# nails_schematic_v2.net
KiCad netlist of a schematic drawn in Altium Designer
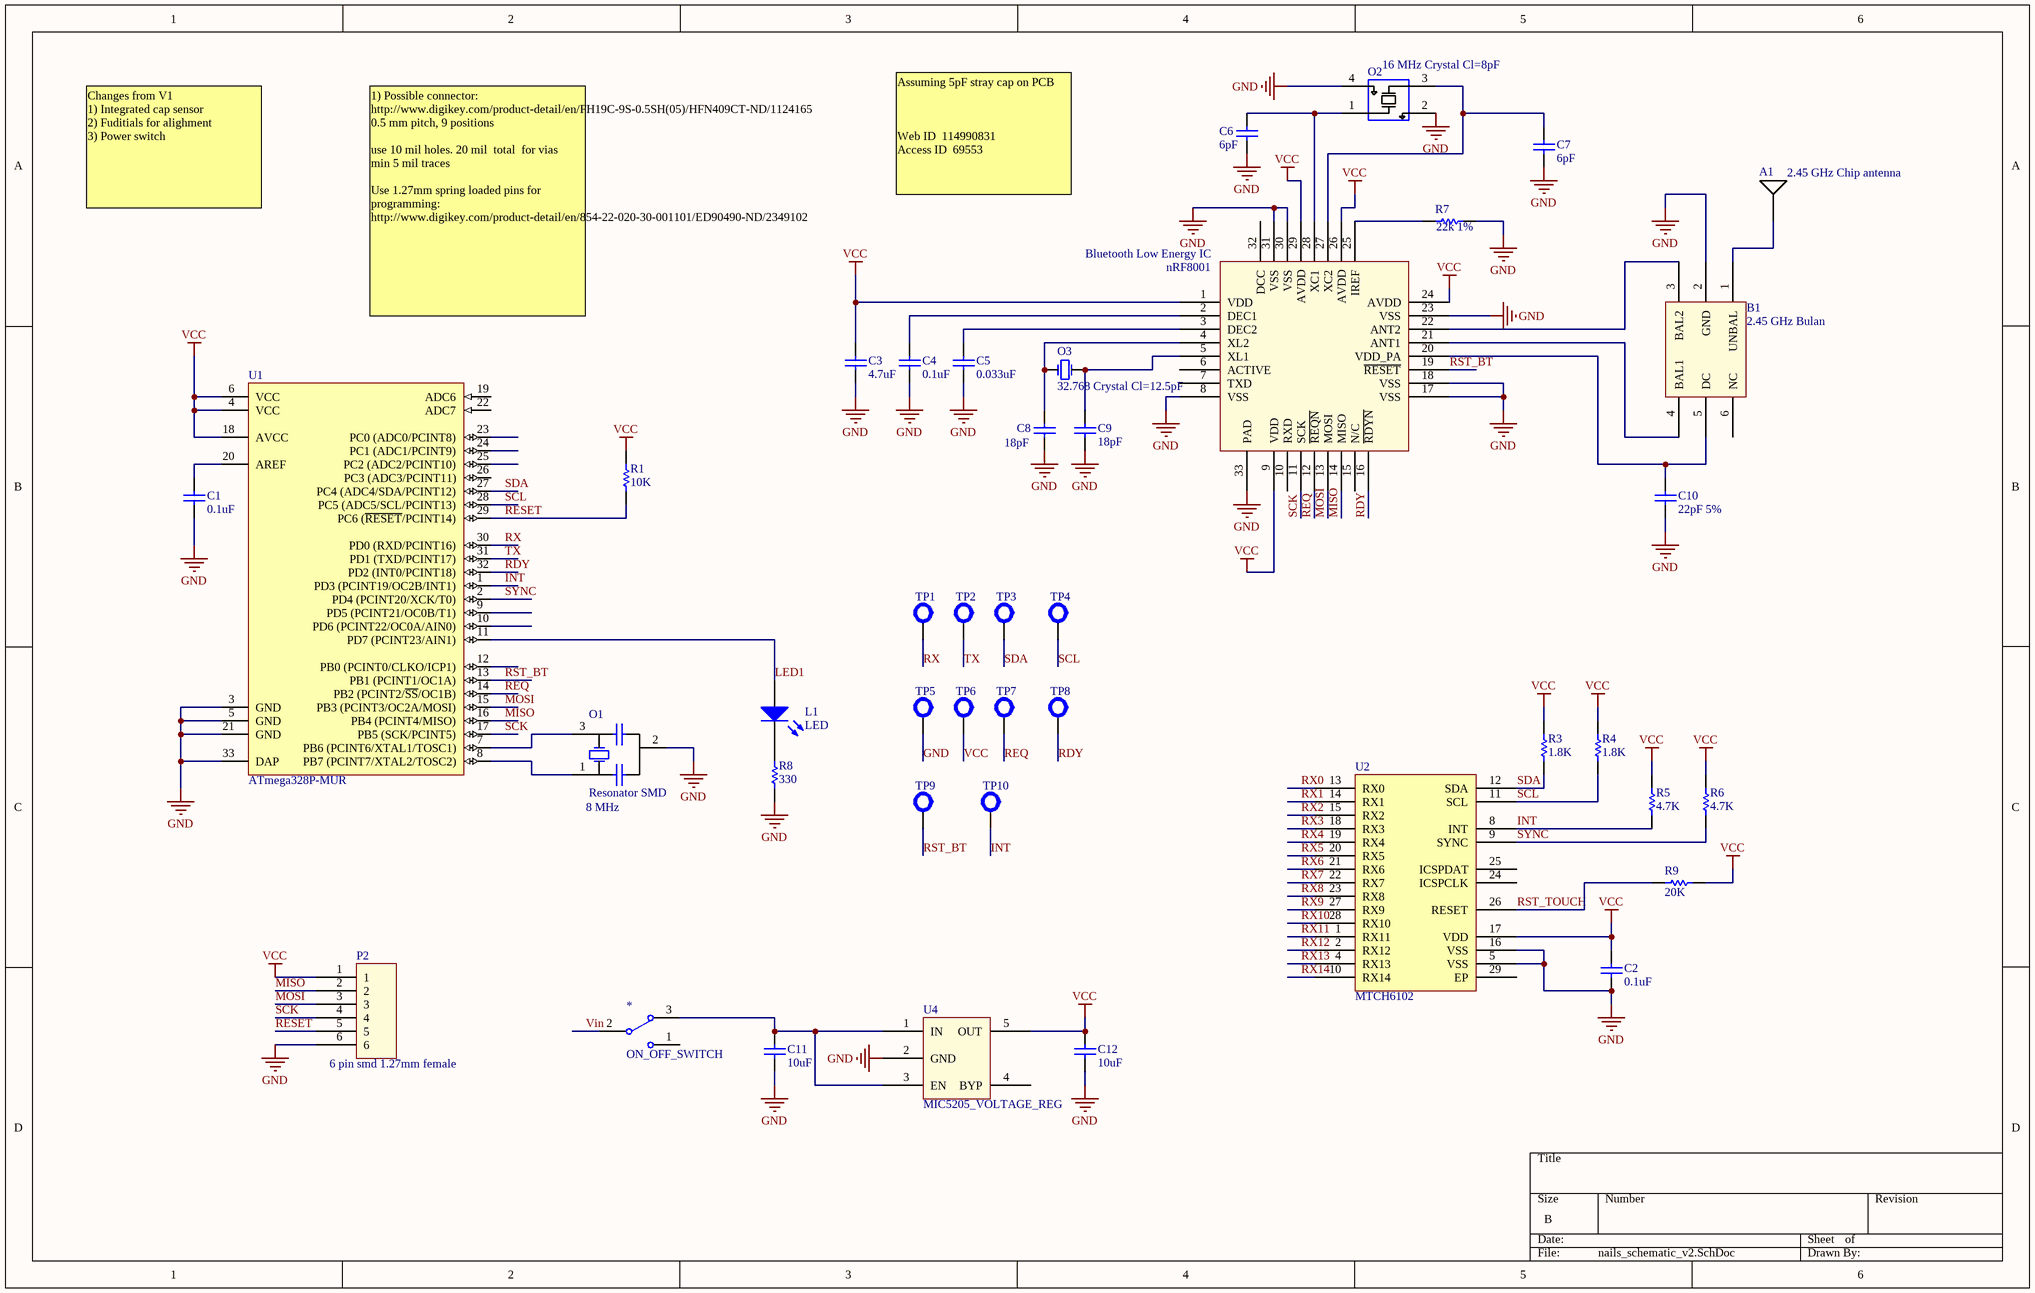
[diagram p0: nails_schematic_v2.SchDoc]

(export (version "E")
  (design (tool "Eeschema 10.0.6"))
  (components
    (comp (ref "*")
      (value "ON_OFF_SWITCH")
      (footprint "SWTICH_SMD_SIDE")
      (description "DPDT SMD Side Switch 240 mA at 5V")
      (libsource (lib "Artem_Library") (part "ON_OFF_SWITCH"))
    )
    (comp (ref "A1")
      (value "2.45 GHz Chip antenna")
      (footprint "2450AT18A100E")
      (description "for Bluetooth")
      (libsource (lib "Artem_Library") (part "2.45 GHz Chip antenna"))
    )
    (comp (ref "B1")
      (value "2.45 GHz Bulan")
      (footprint "2450BM14A0002")
      (description "for nRF8001 chip")
      (libsource (lib "Artem_Library") (part "2.45 GHz Bulan"))
    )
    (comp (ref "Bluetooth Low Energy IC")
      (value "nRF8001")
      (footprint "QFN32_W_GND")
      (libsource (lib "Artem_Library") (part "nRF8001"))
    )
    (comp (ref "C1")
      (value "0.1uF")
      (footprint "0402W")
      (description "SMD Cap 1206")
      (libsource (lib "Artem_Library") (part "Capacitor"))
    )
    (comp (ref "C2")
      (value "0.1uF")
      (footprint "0402W")
      (description "SMD Cap 1206")
      (libsource (lib "Artem_Library") (part "Capacitor"))
    )
    (comp (ref "C3")
      (value "4.7uF")
      (footprint "0402W")
      (description "SMD Cap 1206")
      (libsource (lib "Artem_Library") (part "Capacitor"))
    )
    (comp (ref "C4")
      (value "0.1uF")
      (footprint "0402W")
      (description "SMD Cap 1206")
      (libsource (lib "Artem_Library") (part "Capacitor"))
    )
    (comp (ref "C5")
      (value "0.033uF")
      (footprint "0402W")
      (description "SMD Cap 1206")
      (libsource (lib "Artem_Library") (part "Capacitor"))
    )
    (comp (ref "C6")
      (value "6pF")
      (footprint "0402W")
      (description "SMD Cap 1206")
      (libsource (lib "Artem_Library") (part "Capacitor"))
    )
    (comp (ref "C7")
      (value "6pF")
      (footprint "0402W")
      (description "SMD Cap 1206")
      (libsource (lib "Artem_Library") (part "Capacitor"))
    )
    (comp (ref "C8")
      (value "18pF")
      (footprint "0402W")
      (description "SMD Cap 1206")
      (libsource (lib "Artem_Library") (part "Capacitor"))
    )
    (comp (ref "C9")
      (value "18pF")
      (footprint "0402W")
      (description "SMD Cap 1206")
      (libsource (lib "Artem_Library") (part "Capacitor"))
    )
    (comp (ref "C10")
      (value "22pF 5%")
      (footprint "0402W")
      (description "SMD Cap 1206")
      (libsource (lib "Artem_Library") (part "Capacitor"))
    )
    (comp (ref "C11")
      (value "10uF")
      (footprint "0402W")
      (description "SMD Cap 1206")
      (libsource (lib "Artem_Library") (part "Capacitor"))
    )
    (comp (ref "C12")
      (value "10uF")
      (footprint "0402W")
      (description "SMD Cap 1206")
      (libsource (lib "Artem_Library") (part "Capacitor"))
    )
    (comp (ref "L1")
      (value "LED")
      (footprint "0402W")
      (description "LED SMD 1206/0603")
      (libsource (lib "Artem_Library") (part "LED"))
    )
    (comp (ref "O1")
      (value "Resonator SMD")
      (footprint "Resonator SMD")
      (description "Build in caps")
      (libsource (lib "Artem_Library") (part "Resonator SMD"))
    )
    (comp (ref "O2")
      (value "16 MHz Crystal Cl=8pF")
      (footprint "2.5 x 2.0 crystal")
      (description "For BLE use")
      (libsource (lib "Artem_Library") (part "16 MHz Crystal Wireless"))
    )
    (comp (ref "O3")
      (value "32.768 Crystal Cl=12.5pF")
      (footprint "32.768 Crystal")
      (libsource (lib "Artem_Library") (part "32.768 Crystal"))
    )
    (comp (ref "P2")
      (value "6 pin smd 1.27mm female")
      (footprint "6pos 1.27mm")
      (libsource (lib "Artem_Library") (part "6 pin smd 1.27mm female"))
    )
    (comp (ref "R1") (value "10K") (footprint "0402W") (libsource (lib "Artem_Library") (part "Resistor")))
    (comp (ref "R3") (value "1.8K") (footprint "0402W") (libsource (lib "Artem_Library") (part "Resistor")))
    (comp (ref "R4") (value "1.8K") (footprint "0402W") (libsource (lib "Artem_Library") (part "Resistor")))
    (comp (ref "R5") (value "4.7K") (footprint "0402W") (libsource (lib "Artem_Library") (part "Resistor")))
    (comp (ref "R6") (value "4.7K") (footprint "0402W") (libsource (lib "Artem_Library") (part "Resistor")))
    (comp (ref "R7") (value "22k 1%") (footprint "0402W") (libsource (lib "Artem_Library") (part "Resistor")))
    (comp (ref "R8") (value "330") (footprint "0402W") (libsource (lib "Artem_Library") (part "Resistor")))
    (comp (ref "R9") (value "20K") (footprint "0402W") (libsource (lib "Artem_Library") (part "Resistor")))
    (comp (ref "TP1")
      (value "Test point small")
      (footprint "TEST POINT SMD SUPER SMALL")
      (libsource (lib "Artem_Library") (part "Test point small"))
    )
    (comp (ref "TP2")
      (value "Test point small")
      (footprint "TEST POINT SMD SUPER SMALL")
      (libsource (lib "Artem_Library") (part "Test point small"))
    )
    (comp (ref "TP3")
      (value "Test point small")
      (footprint "TEST POINT SMD SUPER SMALL")
      (libsource (lib "Artem_Library") (part "Test point small"))
    )
    (comp (ref "TP4")
      (value "Test point small")
      (footprint "TEST POINT SMD SUPER SMALL")
      (libsource (lib "Artem_Library") (part "Test point small"))
    )
    (comp (ref "TP5")
      (value "Test point small")
      (footprint "TEST POINT SMD SUPER SMALL")
      (libsource (lib "Artem_Library") (part "Test point small"))
    )
    (comp (ref "TP6")
      (value "Test point small")
      (footprint "TEST POINT SMD SUPER SMALL")
      (libsource (lib "Artem_Library") (part "Test point small"))
    )
    (comp (ref "TP7")
      (value "Test point small")
      (footprint "TEST POINT SMD SUPER SMALL")
      (libsource (lib "Artem_Library") (part "Test point small"))
    )
    (comp (ref "TP8")
      (value "Test point small")
      (footprint "TEST POINT SMD SUPER SMALL")
      (libsource (lib "Artem_Library") (part "Test point small"))
    )
    (comp (ref "TP9")
      (value "Test point small")
      (footprint "TEST POINT SMD SUPER SMALL")
      (libsource (lib "Artem_Library") (part "Test point small"))
    )
    (comp (ref "TP10")
      (value "Test point small")
      (footprint "TEST POINT SMD SUPER SMALL")
      (libsource (lib "Artem_Library") (part "Test point small"))
    )
    (comp (ref "U1")
      (value "ATmega328P-MUR")
      (footprint "32M1-A_M")
      (libsource (lib "Atmel Microcontroller 8-Bit megaAVR") (part "ATmega328P-MUR"))
    )
    (comp (ref "U2")
      (value "MTCH6102")
      (footprint "QFN28_no_gnd_conn")
      (libsource (lib "Artem_Library") (part "MTCH6102"))
    )
    (comp (ref "U4")
      (value "MIC5205_VOLTAGE_REG")
      (footprint "SOT-23-5")
      (description "5V LDO SMD")
      (libsource (lib "Artem_Library") (part "MIC5205_VOLTAGE_REG"))
    )
  )
  (nets
    (net (code "1") (name "/INT") (class "Default")
      (node (ref "R5") (pin "1") (pinfunction "1_1") (pintype "passive"))
      (node (ref "TP10") (pin "0") (pinfunction "0_0") (pintype "passive"))
      (node (ref "U1") (pin "1") (pinfunction "PD3_(PCINT19/OC2B/INT1)_1") (pintype "bidirectional"))
      (node (ref "U2") (pin "8") (pinfunction "INT_8") (pintype "passive"))
    )
    (net (code "2") (name "/LED1") (class "Default")
      (node (ref "L1") (pin "1") (pinfunction "A_1") (pintype "passive"))
      (node (ref "U1") (pin "11") (pinfunction "PD7_(PCINT23/AIN1)_11") (pintype "bidirectional"))
    )
    (net (code "3") (name "/MISO") (class "Default")
      (node (ref "Bluetooth Low Energy IC") (pin "14") (pinfunction "MISO_14") (pintype "passive"))
      (node (ref "P2") (pin "2") (pinfunction "2_2") (pintype "passive"))
      (node (ref "U1") (pin "16") (pinfunction "PB4_(PCINT4/MISO)_16") (pintype "bidirectional"))
    )
    (net (code "4") (name "/MOSI") (class "Default")
      (node (ref "Bluetooth Low Energy IC") (pin "13") (pinfunction "MOSI_13") (pintype "passive"))
      (node (ref "P2") (pin "3") (pinfunction "3_3") (pintype "passive"))
      (node (ref "U1") (pin "15") (pinfunction "PB3_(PCINT3/OC2A/MOSI)_15") (pintype "bidirectional"))
    )
    (net (code "5") (name "/RDY") (class "Default")
      (node (ref "Bluetooth Low Energy IC") (pin "16") (pinfunction "~{RDYN}_16") (pintype "passive"))
      (node (ref "TP8") (pin "0") (pinfunction "0_0") (pintype "passive"))
      (node (ref "U1") (pin "32") (pinfunction "PD2_(INT0/PCINT18)_32") (pintype "bidirectional"))
    )
    (net (code "6") (name "/REQ") (class "Default")
      (node (ref "Bluetooth Low Energy IC") (pin "12") (pinfunction "~{REQN}_12") (pintype "passive"))
      (node (ref "TP7") (pin "0") (pinfunction "0_0") (pintype "passive"))
      (node (ref "U1") (pin "14") (pinfunction "PB2_(PCINT2/~{SS}/OC1B)_14") (pintype "bidirectional"))
    )
    (net (code "7") (name "/RESET") (class "Default")
      (node (ref "P2") (pin "5") (pinfunction "5_5") (pintype "passive"))
      (node (ref "R1") (pin "1") (pinfunction "1_1") (pintype "passive"))
      (node (ref "U1") (pin "29") (pinfunction "PC6_(~{RESET}/PCINT14)_29") (pintype "bidirectional"))
    )
    (net (code "8") (name "/RST_BT") (class "Default")
      (node (ref "Bluetooth Low Energy IC") (pin "19") (pinfunction "~{RESET}_19") (pintype "passive"))
      (node (ref "TP9") (pin "0") (pinfunction "0_0") (pintype "passive"))
      (node (ref "U1") (pin "13") (pinfunction "PB1_(PCINT1/OC1A)_13") (pintype "bidirectional"))
    )
    (net (code "9") (name "/RST_TOUCH") (class "Default")
      (node (ref "R9") (pin "2") (pinfunction "2_2") (pintype "passive"))
      (node (ref "U2") (pin "26") (pinfunction "RESET_26") (pintype "passive"))
    )
    (net (code "10") (name "/RX") (class "Default")
      (node (ref "TP1") (pin "0") (pinfunction "0_0") (pintype "passive"))
      (node (ref "U1") (pin "30") (pinfunction "PD0_(RXD/PCINT16)_30") (pintype "bidirectional"))
    )
    (net (code "11") (name "/RX0") (class "Default")
      (node (ref "U2") (pin "13") (pinfunction "RX0_13") (pintype "passive"))
    )
    (net (code "12") (name "/RX1") (class "Default")
      (node (ref "U2") (pin "14") (pinfunction "RX1_14") (pintype "passive"))
    )
    (net (code "13") (name "/RX2") (class "Default")
      (node (ref "U2") (pin "15") (pinfunction "RX2_15") (pintype "passive"))
    )
    (net (code "14") (name "/RX3") (class "Default")
      (node (ref "U2") (pin "18") (pinfunction "RX3_18") (pintype "passive"))
    )
    (net (code "15") (name "/RX4") (class "Default")
      (node (ref "U2") (pin "19") (pinfunction "RX4_19") (pintype "passive"))
    )
    (net (code "16") (name "/RX5") (class "Default")
      (node (ref "U2") (pin "20") (pinfunction "RX5_20") (pintype "passive"))
    )
    (net (code "17") (name "/RX6") (class "Default")
      (node (ref "U2") (pin "21") (pinfunction "RX6_21") (pintype "passive"))
    )
    (net (code "18") (name "/RX7") (class "Default")
      (node (ref "U2") (pin "22") (pinfunction "RX7_22") (pintype "passive"))
    )
    (net (code "19") (name "/RX8") (class "Default")
      (node (ref "U2") (pin "23") (pinfunction "RX8_23") (pintype "passive"))
    )
    (net (code "20") (name "/RX9") (class "Default")
      (node (ref "U2") (pin "27") (pinfunction "RX9_27") (pintype "passive"))
    )
    (net (code "21") (name "/RX10") (class "Default")
      (node (ref "U2") (pin "28") (pinfunction "RX10_28") (pintype "passive"))
    )
    (net (code "22") (name "/RX11") (class "Default")
      (node (ref "U2") (pin "1") (pinfunction "RX11_1") (pintype "passive"))
    )
    (net (code "23") (name "/RX12") (class "Default")
      (node (ref "U2") (pin "2") (pinfunction "RX12_2") (pintype "passive"))
    )
    (net (code "24") (name "/RX13") (class "Default")
      (node (ref "U2") (pin "4") (pinfunction "RX13_4") (pintype "passive"))
    )
    (net (code "25") (name "/RX14") (class "Default")
      (node (ref "U2") (pin "10") (pinfunction "RX14_10") (pintype "passive"))
    )
    (net (code "26") (name "/SCK") (class "Default")
      (node (ref "Bluetooth Low Energy IC") (pin "11") (pinfunction "SCK_11") (pintype "passive"))
      (node (ref "P2") (pin "4") (pinfunction "4_4") (pintype "passive"))
      (node (ref "U1") (pin "17") (pinfunction "PB5_(SCK/PCINT5)_17") (pintype "bidirectional"))
    )
    (net (code "27") (name "/SCL") (class "Default")
      (node (ref "R4") (pin "1") (pinfunction "1_1") (pintype "passive"))
      (node (ref "TP4") (pin "0") (pinfunction "0_0") (pintype "passive"))
      (node (ref "U1") (pin "28") (pinfunction "PC5_(ADC5/SCL/PCINT13)_28") (pintype "bidirectional"))
      (node (ref "U2") (pin "11") (pinfunction "SCL_11") (pintype "passive"))
    )
    (net (code "28") (name "/SDA") (class "Default")
      (node (ref "R3") (pin "1") (pinfunction "1_1") (pintype "passive"))
      (node (ref "TP3") (pin "0") (pinfunction "0_0") (pintype "passive"))
      (node (ref "U1") (pin "27") (pinfunction "PC4_(ADC4/SDA/PCINT12)_27") (pintype "bidirectional"))
      (node (ref "U2") (pin "12") (pinfunction "SDA_12") (pintype "passive"))
    )
    (net (code "29") (name "/SYNC") (class "Default")
      (node (ref "R6") (pin "1") (pinfunction "1_1") (pintype "passive"))
      (node (ref "U1") (pin "2") (pinfunction "PD4_(PCINT20/XCK/T0)_2") (pintype "bidirectional"))
      (node (ref "U2") (pin "9") (pinfunction "SYNC_9") (pintype "passive"))
    )
    (net (code "30") (name "/TX") (class "Default")
      (node (ref "TP2") (pin "0") (pinfunction "0_0") (pintype "passive"))
      (node (ref "U1") (pin "31") (pinfunction "PD1_(TXD/PCINT17)_31") (pintype "bidirectional"))
    )
    (net (code "31") (name "/Vin") (class "Default")
      (node (ref "*") (pin "2") (pinfunction "2_2") (pintype "passive"))
    )
    (net (code "32") (name "GND") (class "Default")
      (node (ref "B1") (pin "2") (pinfunction "GND_2") (pintype "passive"))
      (node (ref "Bluetooth Low Energy IC") (pin "17") (pinfunction "VSS_17") (pintype "passive"))
      (node (ref "Bluetooth Low Energy IC") (pin "18") (pinfunction "VSS_18") (pintype "passive"))
      (node (ref "Bluetooth Low Energy IC") (pin "23") (pinfunction "VSS_23") (pintype "passive"))
      (node (ref "Bluetooth Low Energy IC") (pin "30") (pinfunction "VSS_30") (pintype "passive"))
      (node (ref "Bluetooth Low Energy IC") (pin "31") (pinfunction "VSS_31") (pintype "passive"))
      (node (ref "Bluetooth Low Energy IC") (pin "33") (pinfunction "PAD_33") (pintype "passive"))
      (node (ref "Bluetooth Low Energy IC") (pin "8") (pinfunction "VSS_8") (pintype "passive"))
      (node (ref "C1") (pin "1") (pinfunction "1_1") (pintype "passive"))
      (node (ref "C10") (pin "1") (pinfunction "1_1") (pintype "passive"))
      (node (ref "C11") (pin "1") (pinfunction "1_1") (pintype "passive"))
      (node (ref "C12") (pin "1") (pinfunction "1_1") (pintype "passive"))
      (node (ref "C2") (pin "1") (pinfunction "1_1") (pintype "passive"))
      (node (ref "C3") (pin "1") (pinfunction "1_1") (pintype "passive"))
      (node (ref "C4") (pin "1") (pinfunction "1_1") (pintype "passive"))
      (node (ref "C5") (pin "1") (pinfunction "1_1") (pintype "passive"))
      (node (ref "C6") (pin "1") (pinfunction "1_1") (pintype "passive"))
      (node (ref "C7") (pin "1") (pinfunction "1_1") (pintype "passive"))
      (node (ref "C8") (pin "1") (pinfunction "1_1") (pintype "passive"))
      (node (ref "C9") (pin "1") (pinfunction "1_1") (pintype "passive"))
      (node (ref "O1") (pin "2") (pinfunction "2_2") (pintype "passive"))
      (node (ref "O2") (pin "2") (pinfunction "Gnd_2") (pintype "passive"))
      (node (ref "O2") (pin "4") (pinfunction "Gnd_4") (pintype "passive"))
      (node (ref "P2") (pin "6") (pinfunction "6_6") (pintype "passive"))
      (node (ref "R7") (pin "1") (pinfunction "1_1") (pintype "passive"))
      (node (ref "R8") (pin "1") (pinfunction "1_1") (pintype "passive"))
      (node (ref "TP5") (pin "0") (pinfunction "0_0") (pintype "passive"))
      (node (ref "U1") (pin "21") (pinfunction "GND_21") (pintype "power_in"))
      (node (ref "U1") (pin "3") (pinfunction "GND_3") (pintype "power_in"))
      (node (ref "U1") (pin "33") (pinfunction "DAP_33") (pintype "power_in"))
      (node (ref "U1") (pin "5") (pinfunction "GND_5") (pintype "power_in"))
      (node (ref "U2") (pin "16") (pinfunction "VSS_16") (pintype "passive"))
      (node (ref "U2") (pin "5") (pinfunction "VSS_5") (pintype "passive"))
      (node (ref "U4") (pin "2") (pinfunction "GND_2") (pintype "passive"))
    )
    (net (code "33") (name "Net-(B1-BAL1)") (class "Default")
      (node (ref "B1") (pin "4") (pinfunction "BAL1_4") (pintype "passive"))
      (node (ref "Bluetooth Low Energy IC") (pin "21") (pinfunction "ANT1_21") (pintype "passive"))
    )
    (net (code "34") (name "Net-(B1-BAL2)") (class "Default")
      (node (ref "B1") (pin "3") (pinfunction "BAL2_3") (pintype "passive"))
      (node (ref "Bluetooth Low Energy IC") (pin "22") (pinfunction "ANT2_22") (pintype "passive"))
    )
    (net (code "35") (name "Net-(B1-DC)") (class "Default")
      (node (ref "B1") (pin "5") (pinfunction "DC_5") (pintype "passive"))
      (node (ref "Bluetooth Low Energy IC") (pin "20") (pinfunction "VDD_PA_20") (pintype "passive"))
      (node (ref "C10") (pin "2") (pinfunction "2_2") (pintype "passive"))
    )
    (net (code "36") (name "Net-(B1-UNBAL)") (class "Default")
      (node (ref "A1") (pin "1") (pinfunction "1_1") (pintype "passive"))
      (node (ref "B1") (pin "1") (pinfunction "UNBAL_1") (pintype "passive"))
    )
    (net (code "37") (name "Net-(Bluetooth Low Energy IC-DEC1)") (class "Default")
      (node (ref "Bluetooth Low Energy IC") (pin "2") (pinfunction "DEC1_2") (pintype "passive"))
      (node (ref "C4") (pin "2") (pinfunction "2_2") (pintype "passive"))
    )
    (net (code "38") (name "Net-(Bluetooth Low Energy IC-DEC2)") (class "Default")
      (node (ref "Bluetooth Low Energy IC") (pin "3") (pinfunction "DEC2_3") (pintype "passive"))
      (node (ref "C5") (pin "2") (pinfunction "2_2") (pintype "passive"))
    )
    (net (code "39") (name "Net-(Bluetooth Low Energy IC-IREF)") (class "Default")
      (node (ref "Bluetooth Low Energy IC") (pin "25") (pinfunction "IREF_25") (pintype "passive"))
      (node (ref "R7") (pin "2") (pinfunction "2_2") (pintype "passive"))
    )
    (net (code "40") (name "Net-(Bluetooth Low Energy IC-XC1)") (class "Default")
      (node (ref "Bluetooth Low Energy IC") (pin "28") (pinfunction "XC1_28") (pintype "passive"))
      (node (ref "C6") (pin "2") (pinfunction "2_2") (pintype "passive"))
      (node (ref "O2") (pin "1") (pinfunction "XIN_1") (pintype "passive"))
    )
    (net (code "41") (name "Net-(Bluetooth Low Energy IC-XC2)") (class "Default")
      (node (ref "Bluetooth Low Energy IC") (pin "27") (pinfunction "XC2_27") (pintype "passive"))
      (node (ref "C7") (pin "2") (pinfunction "2_2") (pintype "passive"))
      (node (ref "O2") (pin "3") (pinfunction "XOUT_3") (pintype "passive"))
    )
    (net (code "42") (name "Net-(Bluetooth Low Energy IC-XL1)") (class "Default")
      (node (ref "Bluetooth Low Energy IC") (pin "5") (pinfunction "XL1_5") (pintype "passive"))
      (node (ref "C9") (pin "2") (pinfunction "2_2") (pintype "passive"))
      (node (ref "O3") (pin "2") (pinfunction "2_2") (pintype "passive"))
    )
    (net (code "43") (name "Net-(Bluetooth Low Energy IC-XL2)") (class "Default")
      (node (ref "Bluetooth Low Energy IC") (pin "4") (pinfunction "XL2_4") (pintype "passive"))
      (node (ref "C8") (pin "2") (pinfunction "2_2") (pintype "passive"))
      (node (ref "O3") (pin "1") (pinfunction "1_1") (pintype "passive"))
    )
    (net (code "44") (name "Net-(L1-K)") (class "Default")
      (node (ref "L1") (pin "2") (pinfunction "K_2") (pintype "passive"))
      (node (ref "R8") (pin "2") (pinfunction "2_2") (pintype "passive"))
    )
    (net (code "45") (name "Net-(U1-AREF)") (class "Default")
      (node (ref "C1") (pin "2") (pinfunction "2_2") (pintype "passive"))
      (node (ref "U1") (pin "20") (pinfunction "AREF_20") (pintype "passive"))
    )
    (net (code "46") (name "Net-(U1-PB6_(PCINT6{slash}XTAL1{slash}TOSC1))") (class "Default")
      (node (ref "O1") (pin "3") (pinfunction "3_3") (pintype "passive"))
      (node (ref "U1") (pin "7") (pinfunction "PB6_(PCINT6/XTAL1/TOSC1)_7") (pintype "bidirectional"))
    )
    (net (code "47") (name "Net-(U1-PB7_(PCINT7{slash}XTAL2{slash}TOSC2))") (class "Default")
      (node (ref "O1") (pin "1") (pinfunction "1_1") (pintype "passive"))
      (node (ref "U1") (pin "8") (pinfunction "PB7_(PCINT7/XTAL2/TOSC2)_8") (pintype "bidirectional"))
    )
    (net (code "48") (name "Net-(U4-EN)") (class "Default")
      (node (ref "*") (pin "3") (pinfunction "3_3") (pintype "passive"))
      (node (ref "C11") (pin "2") (pinfunction "2_2") (pintype "passive"))
      (node (ref "U4") (pin "1") (pinfunction "IN_1") (pintype "passive"))
      (node (ref "U4") (pin "3") (pinfunction "EN_3") (pintype "passive"))
    )
    (net (code "49") (name "VCC") (class "Default")
      (node (ref "Bluetooth Low Energy IC") (pin "1") (pinfunction "VDD_1") (pintype "passive"))
      (node (ref "Bluetooth Low Energy IC") (pin "24") (pinfunction "AVDD_24") (pintype "passive"))
      (node (ref "Bluetooth Low Energy IC") (pin "26") (pinfunction "AVDD_26") (pintype "passive"))
      (node (ref "Bluetooth Low Energy IC") (pin "29") (pinfunction "AVDD_29") (pintype "passive"))
      (node (ref "Bluetooth Low Energy IC") (pin "9") (pinfunction "VDD_9") (pintype "passive"))
      (node (ref "C12") (pin "2") (pinfunction "2_2") (pintype "passive"))
      (node (ref "C2") (pin "2") (pinfunction "2_2") (pintype "passive"))
      (node (ref "C3") (pin "2") (pinfunction "2_2") (pintype "passive"))
      (node (ref "P2") (pin "1") (pinfunction "1_1") (pintype "passive"))
      (node (ref "R1") (pin "2") (pinfunction "2_2") (pintype "passive"))
      (node (ref "R3") (pin "2") (pinfunction "2_2") (pintype "passive"))
      (node (ref "R4") (pin "2") (pinfunction "2_2") (pintype "passive"))
      (node (ref "R5") (pin "2") (pinfunction "2_2") (pintype "passive"))
      (node (ref "R6") (pin "2") (pinfunction "2_2") (pintype "passive"))
      (node (ref "R9") (pin "1") (pinfunction "1_1") (pintype "passive"))
      (node (ref "TP6") (pin "0") (pinfunction "0_0") (pintype "passive"))
      (node (ref "U1") (pin "18") (pinfunction "AVCC_18") (pintype "power_in"))
      (node (ref "U1") (pin "4") (pinfunction "VCC_4") (pintype "power_in"))
      (node (ref "U1") (pin "6") (pinfunction "VCC_6") (pintype "power_in"))
      (node (ref "U2") (pin "17") (pinfunction "VDD_17") (pintype "passive"))
      (node (ref "U4") (pin "5") (pinfunction "OUT_5") (pintype "passive"))
    )
    (net (code "50") (name "unconnected-(*-Pad1)") (class "Default")
      (node (ref "*") (pin "1") (pinfunction "1_1") (pintype "passive"))
    )
    (net (code "51") (name "unconnected-(B1-NC-Pad6)") (class "Default")
      (node (ref "B1") (pin "6") (pinfunction "NC_6") (pintype "passive"))
    )
    (net (code "52") (name "unconnected-(Bluetooth Low Energy IC-ACTIVE-Pad6)") (class "Default")
      (node (ref "Bluetooth Low Energy IC") (pin "6") (pinfunction "ACTIVE_6") (pintype "passive"))
    )
    (net (code "53") (name "unconnected-(Bluetooth Low Energy IC-DCC-Pad32)") (class "Default")
      (node (ref "Bluetooth Low Energy IC") (pin "32") (pinfunction "DCC_32") (pintype "passive"))
    )
    (net (code "54") (name "unconnected-(Bluetooth Low Energy IC-N{slash}C-Pad15)") (class "Default")
      (node (ref "Bluetooth Low Energy IC") (pin "15") (pinfunction "N/C_15") (pintype "passive"))
    )
    (net (code "55") (name "unconnected-(Bluetooth Low Energy IC-RXD-Pad10)") (class "Default")
      (node (ref "Bluetooth Low Energy IC") (pin "10") (pinfunction "RXD_10") (pintype "passive"))
    )
    (net (code "56") (name "unconnected-(Bluetooth Low Energy IC-TXD-Pad7)") (class "Default")
      (node (ref "Bluetooth Low Energy IC") (pin "7") (pinfunction "TXD_7") (pintype "passive"))
    )
    (net (code "57") (name "unconnected-(U1-ADC6-Pad19)") (class "Default")
      (node (ref "U1") (pin "19") (pinfunction "ADC6_19") (pintype "input"))
    )
    (net (code "58") (name "unconnected-(U1-ADC7-Pad22)") (class "Default")
      (node (ref "U1") (pin "22") (pinfunction "ADC7_22") (pintype "input"))
    )
    (net (code "59") (name "unconnected-(U1-PB0_(PCINT0{slash}CLKO{slash}ICP1)-Pad12)") (class "Default")
      (node (ref "U1") (pin "12") (pinfunction "PB0_(PCINT0/CLKO/ICP1)_12") (pintype "bidirectional"))
    )
    (net (code "60") (name "unconnected-(U1-PC0_(ADC0{slash}PCINT8)-Pad23)") (class "Default")
      (node (ref "U1") (pin "23") (pinfunction "PC0_(ADC0/PCINT8)_23") (pintype "bidirectional"))
    )
    (net (code "61") (name "unconnected-(U1-PC1_(ADC1{slash}PCINT9)-Pad24)") (class "Default")
      (node (ref "U1") (pin "24") (pinfunction "PC1_(ADC1/PCINT9)_24") (pintype "bidirectional"))
    )
    (net (code "62") (name "unconnected-(U1-PC2_(ADC2{slash}PCINT10)-Pad25)") (class "Default")
      (node (ref "U1") (pin "25") (pinfunction "PC2_(ADC2/PCINT10)_25") (pintype "bidirectional"))
    )
    (net (code "63") (name "unconnected-(U1-PC3_(ADC3{slash}PCINT11)-Pad26)") (class "Default")
      (node (ref "U1") (pin "26") (pinfunction "PC3_(ADC3/PCINT11)_26") (pintype "bidirectional"))
    )
    (net (code "64") (name "unconnected-(U1-PD5_(PCINT21{slash}OC0B{slash}T1)-Pad9)") (class "Default")
      (node (ref "U1") (pin "9") (pinfunction "PD5_(PCINT21/OC0B/T1)_9") (pintype "bidirectional"))
    )
    (net (code "65") (name "unconnected-(U1-PD6_(PCINT22{slash}OC0A{slash}AIN0)-Pad10)") (class "Default")
      (node (ref "U1") (pin "10") (pinfunction "PD6_(PCINT22/OC0A/AIN0)_10") (pintype "bidirectional"))
    )
    (net (code "66") (name "unconnected-(U2-EP-Pad29)") (class "Default")
      (node (ref "U2") (pin "29") (pinfunction "EP_29") (pintype "passive"))
    )
    (net (code "67") (name "unconnected-(U2-ICSPCLK-Pad24)") (class "Default")
      (node (ref "U2") (pin "24") (pinfunction "ICSPCLK_24") (pintype "passive"))
    )
    (net (code "68") (name "unconnected-(U2-ICSPDAT-Pad25)") (class "Default")
      (node (ref "U2") (pin "25") (pinfunction "ICSPDAT_25") (pintype "passive"))
    )
    (net (code "69") (name "unconnected-(U4-BYP-Pad4)") (class "Default")
      (node (ref "U4") (pin "4") (pinfunction "BYP_4") (pintype "passive"))
    )
  )
)
